# DRIVER_3.net
KiCad netlist of a schematic drawn in Altium Designer
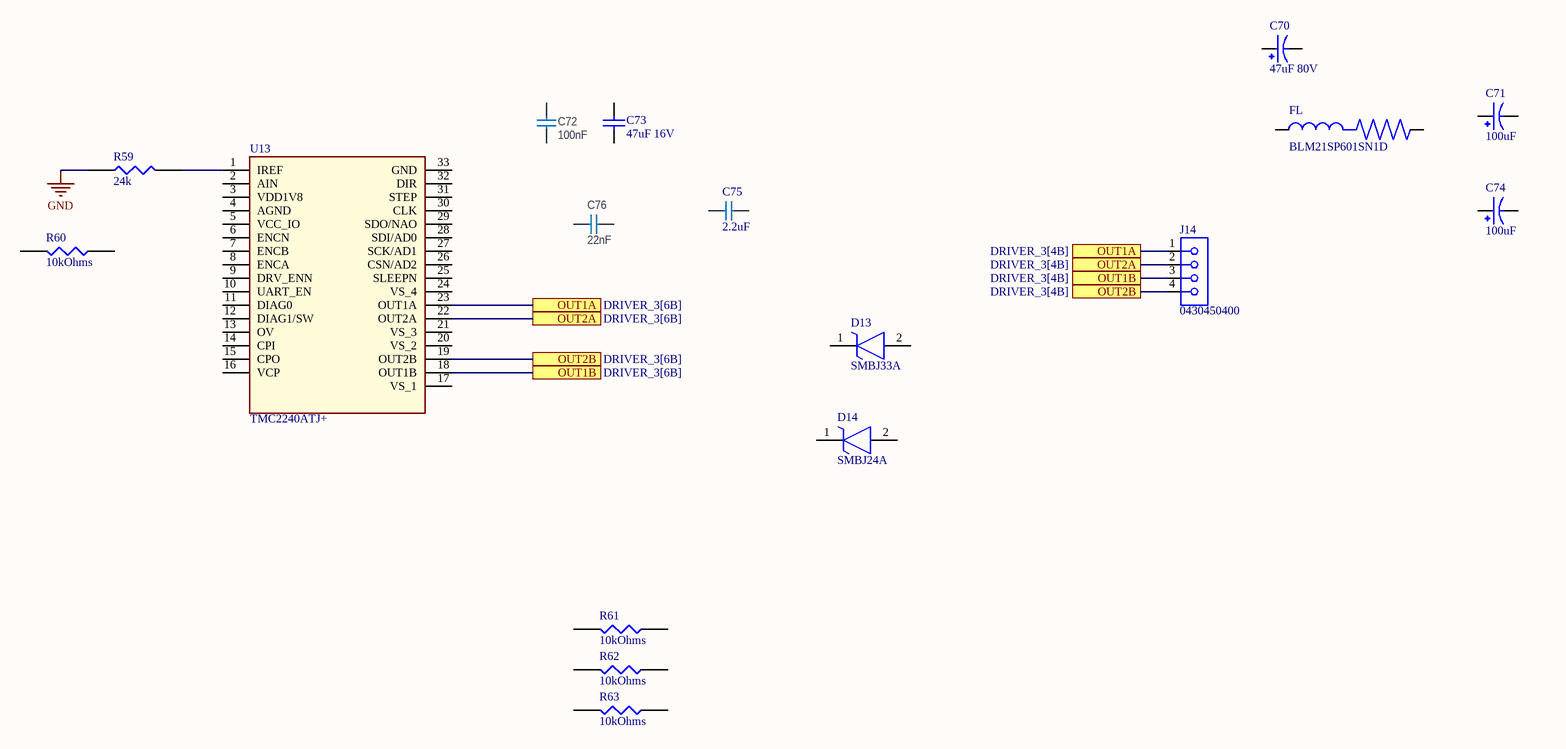
[diagram p0: DRIVER_3.SchDoc]

(export (version "E")
  (design (tool "Eeschema 10.0.6"))
  (components
    (comp (ref "C70")
      (value "47uF 80V")
      (footprint "CAP_EEEFK1K470P")
      (description "47 µF 80 V Aluminum Electrolytic Capacitors Radial, Can - SMD 2000 Hrs @ 105°C")
      (fields (field (name "MANUFACTURER") "Panasonic Industry"))
      (libsource (lib "HW_ADHERENT_SYSCTRL_R1_L1") (part "EEE-FK1K470P"))
    )
    (comp (ref "C71")
      (value "100uF")
      (footprint "CAP_EEEFK1J101P")
      (description "100 µF 63 V Aluminum Electrolytic Capacitors Radial, Can - SMD 2000 Hrs @ 105°C")
      (fields (field (name "MANUFACTURER") "Panasonic Industry"))
      (libsource (lib "HW_ADHERENT_SYSCTRL_R1_L1") (part "EEE-FK1J101P"))
    )
    (comp (ref "C72")
      (value "100nF")
      (footprint "CAPC0603X03L_C")
      (description "Capacitor, Ceramic, X5R, ±10%, 25V")
      (fields
        (field (name "PART NUMBER") "C0201-100n-25V-X5R")
        (field (name "MANUFACTURER") "Murata")
        (field (name "AUTHOR") "rsk")
      )
      (libsource (lib "HW_ADHERENT_SYSCTRL_R1_L1") (part "C0201-100n-25V-X5R"))
    )
    (comp (ref "C73")
      (value "47uF 16V")
      (footprint "CAP1210")
      (description "16V 47uF X5R ±10% 1210 Multilayer Ceramic Capacitors MLCC - SMD/SMT ROHS")
      (fields
        (field (name "MANUFACTURER PART NUMBER") "CS3225X5R476K160NRL")
        (field (name "LCSC PART NUMBER") "C2918513")
      )
      (libsource (lib "HW_ADHERENT_SYSCTRL_R1_L2") (part "CAP1210_47UF_16V"))
    )
    (comp (ref "C74")
      (value "100uF")
      (footprint "CAP_EEEFK1J101P")
      (description "100 µF 63 V Aluminum Electrolytic Capacitors Radial, Can - SMD 2000 Hrs @ 105°C")
      (fields (field (name "MANUFACTURER") "Panasonic Industry"))
      (libsource (lib "HW_ADHERENT_SYSCTRL_R1_L1") (part "EEE-FK1J101P"))
    )
    (comp (ref "C75")
      (value "2.2uF")
      (footprint "CAPC1608X100N")
      (description "2.2 µF ±10% 25V Ceramic Capacitor X5R 0603 (1608 Metric)")
      (fields
        (field (name "MANUFACTURER") "Walsin Technology Corporation")
        (field (name "JLCPCB PART#") "C237194")
      )
      (libsource (lib "HW_ADHERENT_SYSCTRL_R1_L1") (part "0603X225K250CT"))
    )
    (comp (ref "C76")
      (value "22nF")
      (footprint "CAPC0603X03L_C")
      (description "Capacitor, Ceramic, 22nF 10V X5R 0201,±10%")
      (fields
        (field (name "PART NUMBER") "C0201-22n-10V-X5R-GRM033R61A223KE84")
        (field (name "MANUFACTURER") "Murata")
        (field (name "AUTHOR") "prbu")
      )
      (libsource (lib "HW_ADHERENT_SYSCTRL_R1_L2") (part "C0201-22n-10V-X5R-GRM033R61A223KE84_1"))
    )
    (comp (ref "D13")
      (value "SMBJ33A")
      (footprint "SamacSys:SMBJ12A")
      (description "TVS Diode (Uni-directional)")
      (libsource (lib "*") (part "SMBJ33A"))
    )
    (comp (ref "D14")
      (value "SMBJ24A")
      (footprint "SamacSys:SMBJ12A")
      (description "TVS Diode (Uni-directional)")
      (libsource (lib "*") (part "SMBJ24A"))
    )
    (comp (ref "FL")
      (value "BLM21SP601SN1D")
      (footprint "SnapEDApcb:BEADC2012X105N")
      (description "600 Ohms @ 100MHz 1 Power Line Ferrite Bead 0805 _2012 Metric_ 2.3A")
      (fields (field (name "MF") "Murata Electronics North America"))
      (libsource (lib "HW_ADHERENT_SYSCTRL_R1_L1") (part "BLM21SP601SN1D"))
    )
    (comp (ref "J14")
      (value "0430450400")
      (footprint "CONN_SD-43045-001_04_MOL")
      (description "Connector Header Through Hole, Right Angle 4 position 0.118\" (3.00mm)")
      (libsource (lib "HW_ADHERENT_SYSCTRL_R1_L1") (part "0430450400"))
    )
    (comp (ref "R59")
      (value "24k")
      (footprint "0603")
      (description "24 kOhms ±1% 0.1W, 1/10W Chip Resistor 0603 (1608 Metric) Automotive AEC-Q200 Thick Film")
      (fields (field (name "MANUFACTURER") "Stackpole Electronics Inc"))
      (libsource (lib "HW_ADHERENT_SYSCTRL_R1_L1") (part "RMCF0603FT24K0"))
    )
    (comp (ref "R60")
      (value "10kOhms")
      (footprint "RESC0603X03L_C")
      (description "10 kOhms ±1% 0.1W, 1/10W Chip Resistor 0603 (1608 Metric) Automotive AEC-Q200 Thin Film")
      (fields (field (name "MANUFACTURER") "Vishay Dale"))
      (libsource (lib "HW_ADHERENT_SYSCTRL_R1_L1") (part "TNPW060310K0FHTA"))
    )
    (comp (ref "R61")
      (value "10kOhms")
      (footprint "RESC0603X03L_C")
      (description "10 kOhms ±1% 0.1W, 1/10W Chip Resistor 0603 (1608 Metric) Automotive AEC-Q200 Thin Film")
      (fields (field (name "MANUFACTURER") "Vishay Dale"))
      (libsource (lib "HW_ADHERENT_SYSCTRL_R1_L1") (part "TNPW060310K0FHTA"))
    )
    (comp (ref "R62")
      (value "10kOhms")
      (footprint "RESC0603X03L_C")
      (description "10 kOhms ±1% 0.1W, 1/10W Chip Resistor 0603 (1608 Metric) Automotive AEC-Q200 Thin Film")
      (fields (field (name "MANUFACTURER") "Vishay Dale"))
      (libsource (lib "HW_ADHERENT_SYSCTRL_R1_L1") (part "TNPW060310K0FHTA"))
    )
    (comp (ref "R63")
      (value "10kOhms")
      (footprint "RESC0603X03L_C")
      (description "10 kOhms ±1% 0.1W, 1/10W Chip Resistor 0603 (1608 Metric) Automotive AEC-Q200 Thin Film")
      (fields (field (name "MANUFACTURER") "Vishay Dale"))
      (libsource (lib "HW_ADHERENT_SYSCTRL_R1_L1") (part "TNPW060310K0FHTA"))
    )
    (comp (ref "U13")
      (value "TMC2240ATJ+")
      (footprint "QFN50P500X500X80-33N")
      (description "Bipolar Motor Driver Power MOSFET SPI, Step/Direction, UART 32-TQFN (5x5)")
      (fields (field (name "MANUFACTURER") "Analog Devices Inc./Maxim Integrated"))
      (libsource (lib "HW_ADHERENT_SYSCTRL_R1_L1") (part "TMC2240ATJ+"))
    )
  )
  (nets
    (net (code "1") (name "/OUT1A") (class "Default")
      (node (ref "J14") (pin "1") (pinfunction "1_1") (pintype "passive"))
      (node (ref "U13") (pin "23") (pinfunction "OUT1A_23") (pintype "passive"))
    )
    (net (code "2") (name "/OUT1B") (class "Default")
      (node (ref "J14") (pin "3") (pinfunction "3_3") (pintype "passive"))
      (node (ref "U13") (pin "18") (pinfunction "OUT1B_18") (pintype "passive"))
    )
    (net (code "3") (name "/OUT2A") (class "Default")
      (node (ref "J14") (pin "2") (pinfunction "2_2") (pintype "passive"))
      (node (ref "U13") (pin "22") (pinfunction "OUT2A_22") (pintype "passive"))
    )
    (net (code "4") (name "/OUT2B") (class "Default")
      (node (ref "J14") (pin "4") (pinfunction "4_4") (pintype "passive"))
      (node (ref "U13") (pin "19") (pinfunction "OUT2B_19") (pintype "passive"))
    )
    (net (code "5") (name "GND") (class "Default")
      (node (ref "R59") (pin "1") (pinfunction "1_1") (pintype "passive"))
    )
    (net (code "6") (name "Net-(U13-IREF)") (class "Default")
      (node (ref "R59") (pin "2") (pinfunction "2_2") (pintype "passive"))
      (node (ref "U13") (pin "1") (pinfunction "IREF_1") (pintype "passive"))
    )
    (net (code "7") (name "unconnected-(C70-Pad1)") (class "Default")
      (node (ref "C70") (pin "1") (pinfunction "1_1") (pintype "passive"))
    )
    (net (code "8") (name "unconnected-(C70-Pad2)") (class "Default")
      (node (ref "C70") (pin "2") (pinfunction "2_2") (pintype "passive"))
    )
    (net (code "9") (name "unconnected-(C71-Pad1)") (class "Default")
      (node (ref "C71") (pin "1") (pinfunction "1_1") (pintype "passive"))
    )
    (net (code "10") (name "unconnected-(C71-Pad2)") (class "Default")
      (node (ref "C71") (pin "2") (pinfunction "2_2") (pintype "passive"))
    )
    (net (code "11") (name "unconnected-(C72-Pad1)") (class "Default")
      (node (ref "C72") (pin "1") (pinfunction "1_1") (pintype "passive"))
    )
    (net (code "12") (name "unconnected-(C72-Pad2)") (class "Default")
      (node (ref "C72") (pin "2") (pinfunction "2_2") (pintype "passive"))
    )
    (net (code "13") (name "unconnected-(C73-Pad1)") (class "Default")
      (node (ref "C73") (pin "1") (pinfunction "1_1") (pintype "passive"))
    )
    (net (code "14") (name "unconnected-(C73-Pad2)") (class "Default")
      (node (ref "C73") (pin "2") (pinfunction "2_2") (pintype "passive"))
    )
    (net (code "15") (name "unconnected-(C74-Pad1)") (class "Default")
      (node (ref "C74") (pin "1") (pinfunction "1_1") (pintype "passive"))
    )
    (net (code "16") (name "unconnected-(C74-Pad2)") (class "Default")
      (node (ref "C74") (pin "2") (pinfunction "2_2") (pintype "passive"))
    )
    (net (code "17") (name "unconnected-(C75-Pad1)") (class "Default")
      (node (ref "C75") (pin "1") (pinfunction "1_1") (pintype "passive"))
    )
    (net (code "18") (name "unconnected-(C75-Pad2)") (class "Default")
      (node (ref "C75") (pin "2") (pinfunction "2_2") (pintype "passive"))
    )
    (net (code "19") (name "unconnected-(C76-Pad1)") (class "Default")
      (node (ref "C76") (pin "1") (pinfunction "1_1") (pintype "passive"))
    )
    (net (code "20") (name "unconnected-(C76-Pad2)") (class "Default")
      (node (ref "C76") (pin "2") (pinfunction "2_2") (pintype "passive"))
    )
    (net (code "21") (name "unconnected-(D13-A-Pad2)") (class "Default")
      (node (ref "D13") (pin "2") (pinfunction "A_2") (pintype "passive"))
    )
    (net (code "22") (name "unconnected-(D13-K-Pad1)") (class "Default")
      (node (ref "D13") (pin "1") (pinfunction "K_1") (pintype "passive"))
    )
    (net (code "23") (name "unconnected-(D14-A-Pad2)") (class "Default")
      (node (ref "D14") (pin "2") (pinfunction "A_2") (pintype "passive"))
    )
    (net (code "24") (name "unconnected-(D14-K-Pad1)") (class "Default")
      (node (ref "D14") (pin "1") (pinfunction "K_1") (pintype "passive"))
    )
    (net (code "25") (name "unconnected-(FL-Pad1)") (class "Default")
      (node (ref "FL") (pin "1") (pinfunction "1_1") (pintype "passive"))
    )
    (net (code "26") (name "unconnected-(FL-Pad2)") (class "Default")
      (node (ref "FL") (pin "2") (pinfunction "2_2") (pintype "passive"))
    )
    (net (code "27") (name "unconnected-(R60-Pad1)") (class "Default")
      (node (ref "R60") (pin "1") (pinfunction "1_1") (pintype "passive"))
    )
    (net (code "28") (name "unconnected-(R60-Pad2)") (class "Default")
      (node (ref "R60") (pin "2") (pinfunction "2_2") (pintype "passive"))
    )
    (net (code "29") (name "unconnected-(R61-Pad1)") (class "Default")
      (node (ref "R61") (pin "1") (pinfunction "1_1") (pintype "passive"))
    )
    (net (code "30") (name "unconnected-(R61-Pad2)") (class "Default")
      (node (ref "R61") (pin "2") (pinfunction "2_2") (pintype "passive"))
    )
    (net (code "31") (name "unconnected-(R62-Pad1)") (class "Default")
      (node (ref "R62") (pin "1") (pinfunction "1_1") (pintype "passive"))
    )
    (net (code "32") (name "unconnected-(R62-Pad2)") (class "Default")
      (node (ref "R62") (pin "2") (pinfunction "2_2") (pintype "passive"))
    )
    (net (code "33") (name "unconnected-(R63-Pad1)") (class "Default")
      (node (ref "R63") (pin "1") (pinfunction "1_1") (pintype "passive"))
    )
    (net (code "34") (name "unconnected-(R63-Pad2)") (class "Default")
      (node (ref "R63") (pin "2") (pinfunction "2_2") (pintype "passive"))
    )
    (net (code "35") (name "unconnected-(U13-AGND-Pad4)") (class "Default")
      (node (ref "U13") (pin "4") (pinfunction "AGND_4") (pintype "passive"))
    )
    (net (code "36") (name "unconnected-(U13-AIN-Pad2)") (class "Default")
      (node (ref "U13") (pin "2") (pinfunction "AIN_2") (pintype "passive"))
    )
    (net (code "37") (name "unconnected-(U13-CLK-Pad30)") (class "Default")
      (node (ref "U13") (pin "30") (pinfunction "CLK_30") (pintype "passive"))
    )
    (net (code "38") (name "unconnected-(U13-CPI-Pad14)") (class "Default")
      (node (ref "U13") (pin "14") (pinfunction "CPI_14") (pintype "passive"))
    )
    (net (code "39") (name "unconnected-(U13-CPO-Pad15)") (class "Default")
      (node (ref "U13") (pin "15") (pinfunction "CPO_15") (pintype "passive"))
    )
    (net (code "40") (name "unconnected-(U13-CSN{slash}AD2-Pad26)") (class "Default")
      (node (ref "U13") (pin "26") (pinfunction "CSN/AD2_26") (pintype "passive"))
    )
    (net (code "41") (name "unconnected-(U13-DIAG0-Pad11)") (class "Default")
      (node (ref "U13") (pin "11") (pinfunction "DIAG0_11") (pintype "passive"))
    )
    (net (code "42") (name "unconnected-(U13-DIAG1{slash}SW-Pad12)") (class "Default")
      (node (ref "U13") (pin "12") (pinfunction "DIAG1/SW_12") (pintype "passive"))
    )
    (net (code "43") (name "unconnected-(U13-DIR-Pad32)") (class "Default")
      (node (ref "U13") (pin "32") (pinfunction "DIR_32") (pintype "passive"))
    )
    (net (code "44") (name "unconnected-(U13-DRV_ENN-Pad9)") (class "Default")
      (node (ref "U13") (pin "9") (pinfunction "DRV_ENN_9") (pintype "passive"))
    )
    (net (code "45") (name "unconnected-(U13-ENCA-Pad8)") (class "Default")
      (node (ref "U13") (pin "8") (pinfunction "ENCA_8") (pintype "passive"))
    )
    (net (code "46") (name "unconnected-(U13-ENCB-Pad7)") (class "Default")
      (node (ref "U13") (pin "7") (pinfunction "ENCB_7") (pintype "passive"))
    )
    (net (code "47") (name "unconnected-(U13-ENCN-Pad6)") (class "Default")
      (node (ref "U13") (pin "6") (pinfunction "ENCN_6") (pintype "passive"))
    )
    (net (code "48") (name "unconnected-(U13-GND-Pad33)") (class "Default")
      (node (ref "U13") (pin "33") (pinfunction "GND_33") (pintype "passive"))
    )
    (net (code "49") (name "unconnected-(U13-OV-Pad13)") (class "Default")
      (node (ref "U13") (pin "13") (pinfunction "OV_13") (pintype "passive"))
    )
    (net (code "50") (name "unconnected-(U13-SCK{slash}AD1-Pad27)") (class "Default")
      (node (ref "U13") (pin "27") (pinfunction "SCK/AD1_27") (pintype "passive"))
    )
    (net (code "51") (name "unconnected-(U13-SDI{slash}AD0-Pad28)") (class "Default")
      (node (ref "U13") (pin "28") (pinfunction "SDI/AD0_28") (pintype "passive"))
    )
    (net (code "52") (name "unconnected-(U13-SDO{slash}NAO-Pad29)") (class "Default")
      (node (ref "U13") (pin "29") (pinfunction "SDO/NAO_29") (pintype "passive"))
    )
    (net (code "53") (name "unconnected-(U13-SLEEPN-Pad25)") (class "Default")
      (node (ref "U13") (pin "25") (pinfunction "SLEEPN_25") (pintype "passive"))
    )
    (net (code "54") (name "unconnected-(U13-STEP-Pad31)") (class "Default")
      (node (ref "U13") (pin "31") (pinfunction "STEP_31") (pintype "passive"))
    )
    (net (code "55") (name "unconnected-(U13-UART_EN-Pad10)") (class "Default")
      (node (ref "U13") (pin "10") (pinfunction "UART_EN_10") (pintype "passive"))
    )
    (net (code "56") (name "unconnected-(U13-VCC_IO-Pad5)") (class "Default")
      (node (ref "U13") (pin "5") (pinfunction "VCC_IO_5") (pintype "passive"))
    )
    (net (code "57") (name "unconnected-(U13-VCP-Pad16)") (class "Default")
      (node (ref "U13") (pin "16") (pinfunction "VCP_16") (pintype "passive"))
    )
    (net (code "58") (name "unconnected-(U13-VDD1V8-Pad3)") (class "Default")
      (node (ref "U13") (pin "3") (pinfunction "VDD1V8_3") (pintype "passive"))
    )
    (net (code "59") (name "unconnected-(U13-VS_1-Pad17)") (class "Default")
      (node (ref "U13") (pin "17") (pinfunction "VS_1_17") (pintype "passive"))
    )
    (net (code "60") (name "unconnected-(U13-VS_2-Pad20)") (class "Default")
      (node (ref "U13") (pin "20") (pinfunction "VS_2_20") (pintype "passive"))
    )
    (net (code "61") (name "unconnected-(U13-VS_3-Pad21)") (class "Default")
      (node (ref "U13") (pin "21") (pinfunction "VS_3_21") (pintype "passive"))
    )
    (net (code "62") (name "unconnected-(U13-VS_4-Pad24)") (class "Default")
      (node (ref "U13") (pin "24") (pinfunction "VS_4_24") (pintype "passive"))
    )
  )
)
